# signalMapper.net
KiCad netlist of a schematic drawn in EAGLE
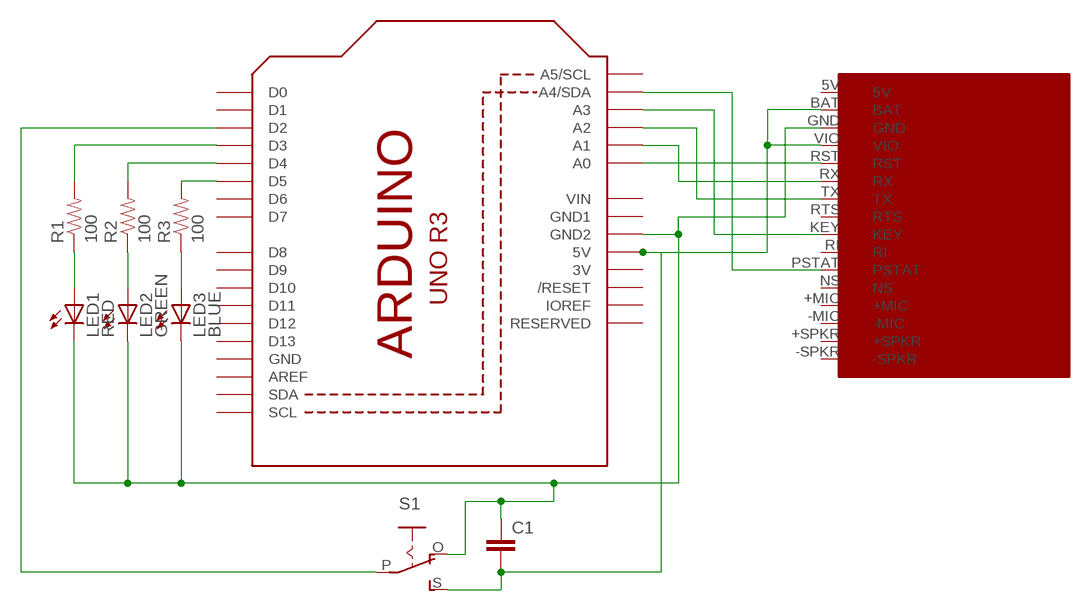
[diagram p0: schematic, sheet 1]

(export (version "E")
  (design (tool "Eeschema 10.0.6"))
  (components
    (comp (ref "C1")
      (value "CAPPTH")
      (footprint "eagle-import:CAP-PTH-SMALL")
      (libsource (lib "eagle-import") (part "CAPPTH"))
    )
    (comp (ref "LED1")
      (value "RED")
      (footprint "eagle-import:LED5MM")
      (libsource (lib "eagle-import") (part "LED5MM"))
    )
    (comp (ref "LED2")
      (value "GREEN")
      (footprint "eagle-import:LED5MM")
      (libsource (lib "eagle-import") (part "LED5MM"))
    )
    (comp (ref "LED3")
      (value "BLUE")
      (footprint "eagle-import:LED5MM")
      (libsource (lib "eagle-import") (part "LED5MM"))
    )
    (comp (ref "R1")
      (value "100")
      (footprint "eagle-import:AXIAL-0.3")
      (libsource (lib "eagle-import") (part "100OHM-1/4W-1%(PTH)"))
    )
    (comp (ref "R2")
      (value "100")
      (footprint "eagle-import:AXIAL-0.3")
      (libsource (lib "eagle-import") (part "100OHM-1/4W-1%(PTH)"))
    )
    (comp (ref "R3")
      (value "100")
      (footprint "eagle-import:AXIAL-0.3")
      (libsource (lib "eagle-import") (part "100OHM-1/4W-1%(PTH)"))
    )
    (comp (ref "S1")
      (value "EG1218S")
      (footprint "eagle-import:EG1218")
      (libsource (lib "eagle-import") (part "EG1218S"))
    )
    (comp (ref "U$1")
      (value "ADAFRUIT_FONA808")
      (footprint "eagle-import:ADAFRUIT_FONA808")
      (libsource (lib "eagle-import") (part "ADAFRUIT_FONA808"))
    )
    (comp (ref "U1")
      (value "ARDUINOR3-BPLACE")
      (footprint "eagle-import:ARDUINOR3-BPLACE")
      (libsource (lib "eagle-import") (part "ARDUINOR3-BPLACE"))
    )
  )
  (nets
    (net (code "1") (name "/3V") (class "Default")
      (node (ref "U1") (pin "3V") (pinfunction "3V_3V") (pintype "power_in"))
    )
    (net (code "2") (name "/5V") (class "Default")
      (node (ref "U$1") (pin "5V") (pinfunction "5V_5V") (pintype "power_in"))
    )
    (net (code "3") (name "/GND") (class "Default")
      (node (ref "U1") (pin "GND") (pinfunction "GND_GND") (pintype "power_in"))
    )
    (net (code "4") (name "/GND1") (class "Default")
      (node (ref "U1") (pin "GND1") (pinfunction "GND1_GND1") (pintype "power_in"))
    )
    (net (code "5") (name "/VIN") (class "Default")
      (node (ref "U1") (pin "VIN") (pinfunction "VIN_VIN") (pintype "power_in"))
    )
    (net (code "6") (name "Net-(C1-Pad2)") (class "Default")
      (node (ref "C1") (pin "2") (pinfunction "2_2") (pintype "passive"))
      (node (ref "S1") (pin "S") (pinfunction "S_S") (pintype "passive"))
      (node (ref "U$1") (pin "BAT") (pinfunction "BAT_BAT") (pintype "power_in"))
      (node (ref "U$1") (pin "VIO") (pinfunction "VIO_VIO") (pintype "power_in"))
      (node (ref "U1") (pin "5V") (pinfunction "5V_5V") (pintype "power_in"))
    )
    (net (code "7") (name "Net-(LED1-C)") (class "Default")
      (node (ref "C1") (pin "1") (pinfunction "1_1") (pintype "passive"))
      (node (ref "LED1") (pin "K") (pinfunction "C_K") (pintype "passive"))
      (node (ref "LED2") (pin "K") (pinfunction "C_K") (pintype "passive"))
      (node (ref "LED3") (pin "K") (pinfunction "C_K") (pintype "passive"))
      (node (ref "S1") (pin "O") (pinfunction "O_O") (pintype "passive"))
      (node (ref "U$1") (pin "GND") (pinfunction "GND_GND") (pintype "power_in"))
      (node (ref "U1") (pin "GND2") (pinfunction "GND2_GND2") (pintype "power_in"))
    )
    (net (code "8") (name "Net-(R1-1)") (class "Default")
      (node (ref "LED1") (pin "A") (pinfunction "A_A") (pintype "passive"))
      (node (ref "R1") (pin "P$1") (pinfunction "1_P$1") (pintype "passive"))
    )
    (net (code "9") (name "Net-(R1-2)") (class "Default")
      (node (ref "R1") (pin "P$2") (pinfunction "2_P$2") (pintype "passive"))
      (node (ref "U1") (pin "D3") (pinfunction "D3_D3") (pintype "bidirectional"))
    )
    (net (code "10") (name "Net-(R2-1)") (class "Default")
      (node (ref "LED2") (pin "A") (pinfunction "A_A") (pintype "passive"))
      (node (ref "R2") (pin "P$1") (pinfunction "1_P$1") (pintype "passive"))
    )
    (net (code "11") (name "Net-(R2-2)") (class "Default")
      (node (ref "R2") (pin "P$2") (pinfunction "2_P$2") (pintype "passive"))
      (node (ref "U1") (pin "D4") (pinfunction "D4_D4") (pintype "bidirectional"))
    )
    (net (code "12") (name "Net-(R3-1)") (class "Default")
      (node (ref "LED3") (pin "A") (pinfunction "A_A") (pintype "passive"))
      (node (ref "R3") (pin "P$1") (pinfunction "1_P$1") (pintype "passive"))
    )
    (net (code "13") (name "Net-(R3-2)") (class "Default")
      (node (ref "R3") (pin "P$2") (pinfunction "2_P$2") (pintype "passive"))
      (node (ref "U1") (pin "D5") (pinfunction "D5_D5") (pintype "bidirectional"))
    )
    (net (code "14") (name "Net-(S1-PadP)") (class "Default")
      (node (ref "S1") (pin "P") (pinfunction "P_P") (pintype "passive"))
      (node (ref "U1") (pin "D2") (pinfunction "D2_D2") (pintype "bidirectional"))
    )
    (net (code "15") (name "Net-(U$1-PadKEY)") (class "Default")
      (node (ref "U$1") (pin "KEY") (pinfunction "KEY_KEY") (pintype "input"))
      (node (ref "U1") (pin "A3") (pinfunction "A3_A3") (pintype "bidirectional"))
    )
    (net (code "16") (name "Net-(U$1-PadRST)") (class "Default")
      (node (ref "U$1") (pin "RST") (pinfunction "RST_RST") (pintype "input"))
      (node (ref "U1") (pin "A0") (pinfunction "A0_A0") (pintype "bidirectional"))
    )
    (net (code "17") (name "Net-(U$1-PadRX)") (class "Default")
      (node (ref "U$1") (pin "RX") (pinfunction "RX_RX") (pintype "input"))
      (node (ref "U1") (pin "A1") (pinfunction "A1_A1") (pintype "bidirectional"))
    )
    (net (code "18") (name "Net-(U$1-PadTX)") (class "Default")
      (node (ref "U$1") (pin "TX") (pinfunction "TX_TX") (pintype "input"))
      (node (ref "U1") (pin "A2") (pinfunction "A2_A2") (pintype "bidirectional"))
    )
    (net (code "19") (name "Net-(U1-A4{slash}SDA)") (class "Default")
      (node (ref "U$1") (pin "PSTAT") (pinfunction "PSTAT_PSTAT") (pintype "output"))
      (node (ref "U1") (pin "A4") (pinfunction "A4/SDA_A4") (pintype "bidirectional"))
    )
    (net (code "20") (name "unconnected-(U$1-Pad+MIC)") (class "Default")
      (node (ref "U$1") (pin "+MIC") (pinfunction "+MIC_+MIC") (pintype "input"))
    )
    (net (code "21") (name "unconnected-(U$1-Pad+SPKR)") (class "Default")
      (node (ref "U$1") (pin "+SPKR") (pinfunction "+SPKR_+SPKR") (pintype "input"))
    )
    (net (code "22") (name "unconnected-(U$1-Pad-MIC)") (class "Default")
      (node (ref "U$1") (pin "-MIC") (pinfunction "-MIC_-MIC") (pintype "input"))
    )
    (net (code "23") (name "unconnected-(U$1-Pad-SPKR)") (class "Default")
      (node (ref "U$1") (pin "-SPKR") (pinfunction "-SPKR_-SPKR") (pintype "input"))
    )
    (net (code "24") (name "unconnected-(U$1-PadNS)") (class "Default")
      (node (ref "U$1") (pin "NS") (pinfunction "NS_NS") (pintype "output"))
    )
    (net (code "25") (name "unconnected-(U$1-PadRI)") (class "Default")
      (node (ref "U$1") (pin "RI") (pinfunction "RI_RI") (pintype "output"))
    )
    (net (code "26") (name "unconnected-(U$1-PadRTS)") (class "Default")
      (node (ref "U$1") (pin "RTS") (pinfunction "RTS_RTS") (pintype "bidirectional"))
    )
    (net (code "27") (name "unconnected-(U1-A5{slash}SCL-PadA5)") (class "Default")
      (node (ref "U1") (pin "A5") (pinfunction "A5/SCL_A5") (pintype "bidirectional"))
    )
    (net (code "28") (name "unconnected-(U1-PadAREF)") (class "Default")
      (node (ref "U1") (pin "AREF") (pinfunction "AREF_AREF") (pintype "bidirectional"))
    )
    (net (code "29") (name "unconnected-(U1-PadD0)") (class "Default")
      (node (ref "U1") (pin "D0") (pinfunction "D0_D0") (pintype "bidirectional"))
    )
    (net (code "30") (name "unconnected-(U1-PadD1)") (class "Default")
      (node (ref "U1") (pin "D1") (pinfunction "D1_D1") (pintype "bidirectional"))
    )
    (net (code "31") (name "unconnected-(U1-PadD6)") (class "Default")
      (node (ref "U1") (pin "D6") (pinfunction "D6_D6") (pintype "bidirectional"))
    )
    (net (code "32") (name "unconnected-(U1-PadD7)") (class "Default")
      (node (ref "U1") (pin "D7") (pinfunction "D7_D7") (pintype "bidirectional"))
    )
    (net (code "33") (name "unconnected-(U1-PadD8)") (class "Default")
      (node (ref "U1") (pin "D8") (pinfunction "D8_D8") (pintype "bidirectional"))
    )
    (net (code "34") (name "unconnected-(U1-PadD9)") (class "Default")
      (node (ref "U1") (pin "D9") (pinfunction "D9_D9") (pintype "bidirectional"))
    )
    (net (code "35") (name "unconnected-(U1-PadD10)") (class "Default")
      (node (ref "U1") (pin "D10") (pinfunction "D10_D10") (pintype "bidirectional"))
    )
    (net (code "36") (name "unconnected-(U1-PadD11)") (class "Default")
      (node (ref "U1") (pin "D11") (pinfunction "D11_D11") (pintype "bidirectional"))
    )
    (net (code "37") (name "unconnected-(U1-PadD12)") (class "Default")
      (node (ref "U1") (pin "D12") (pinfunction "D12_D12") (pintype "bidirectional"))
    )
    (net (code "38") (name "unconnected-(U1-PadD13)") (class "Default")
      (node (ref "U1") (pin "D13") (pinfunction "D13_D13") (pintype "bidirectional"))
    )
    (net (code "39") (name "unconnected-(U1-PadIOREF)") (class "Default")
      (node (ref "U1") (pin "IOREF") (pinfunction "IOREF_IOREF") (pintype "output"))
    )
    (net (code "40") (name "unconnected-(U1-PadRESERVED)") (class "Default")
      (node (ref "U1") (pin "RESERVED") (pinfunction "RESERVED_RESERVED") (pintype "no_connect"))
    )
    (net (code "41") (name "unconnected-(U1-PadSCL)") (class "Default")
      (node (ref "U1") (pin "SCL") (pinfunction "SCL_SCL") (pintype "bidirectional"))
    )
    (net (code "42") (name "unconnected-(U1-PadSDA)") (class "Default")
      (node (ref "U1") (pin "SDA") (pinfunction "SDA_SDA") (pintype "bidirectional"))
    )
    (net (code "43") (name "unconnected-(U1-{slash}RESET-PadRESET)") (class "Default")
      (node (ref "U1") (pin "RESET") (pinfunction "/RESET_RESET") (pintype "bidirectional"))
    )
  )
)
